# DAC_PWW_Outputs.net
KiCad netlist of a schematic drawn in Altium Designer
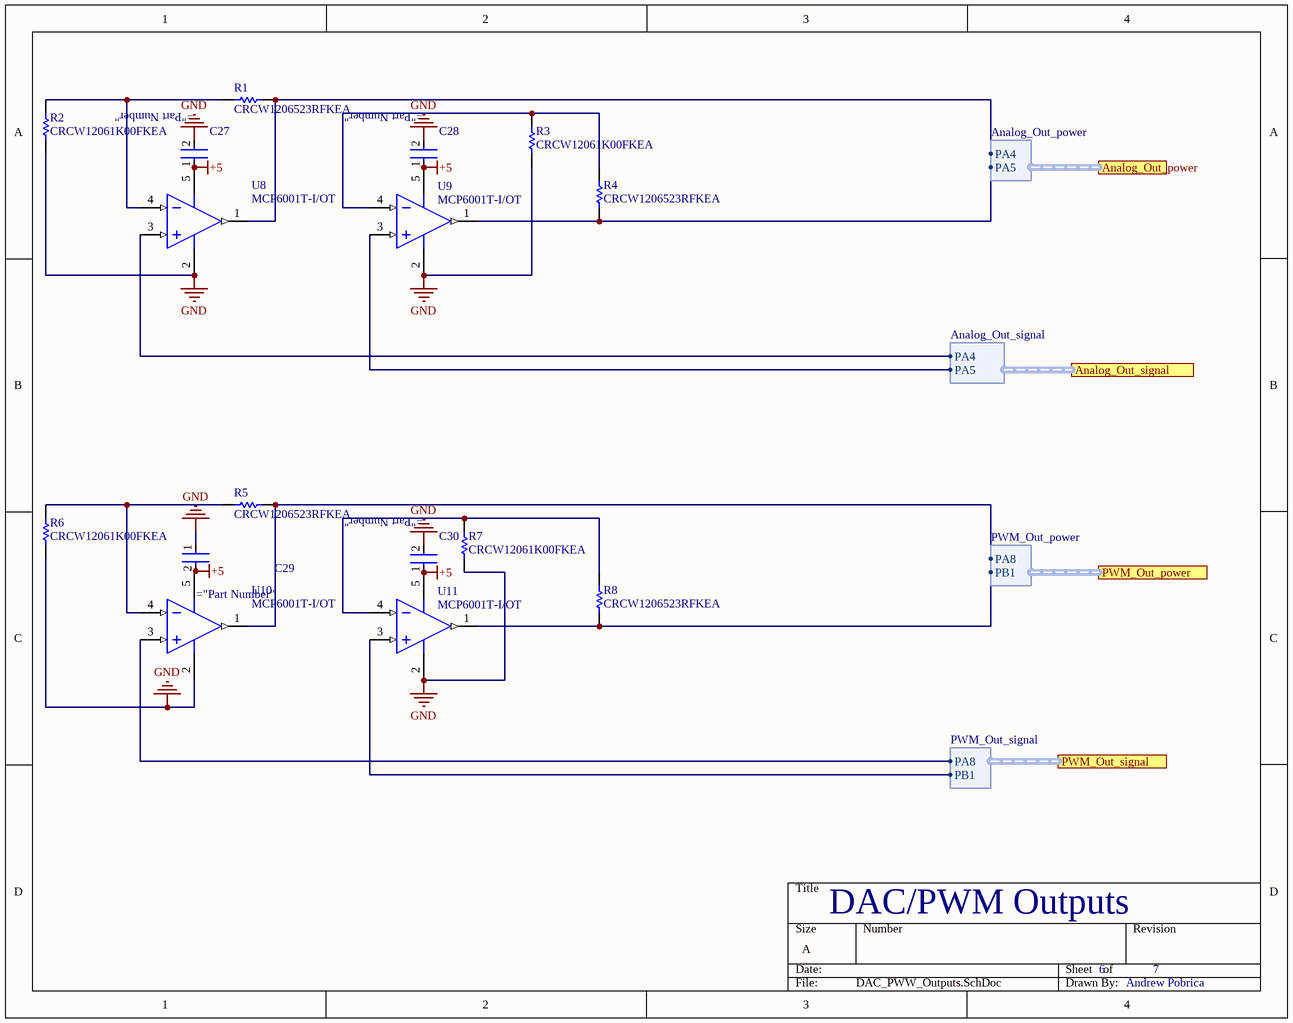
[diagram p0: DAC_PWW_Outputs.SchDoc]

(export (version "E")
  (design (tool "Eeschema 10.0.6"))
  (components
    (comp (ref "C27")
      (value "C0603C104K5RACTU")
      (footprint "Kemet_C0805_IPC_A")
      (libsource (lib "UNK_Kemet_C0603C104K5RACTU_eec") (part "C0603C104K5RACTU"))
    )
    (comp (ref "C28")
      (value "C0603C104K5RACTU")
      (footprint "Kemet_C0805_IPC_A")
      (libsource (lib "UNK_Kemet_C0603C104K5RACTU_eec") (part "C0603C104K5RACTU"))
    )
    (comp (ref "C29")
      (value "C0603C104K5RACTU")
      (footprint "Kemet_C0805_IPC_A")
      (libsource (lib "UNK_Kemet_C0603C104K5RACTU_eec") (part "C0603C104K5RACTU"))
    )
    (comp (ref "C30")
      (value "C0603C104K5RACTU")
      (footprint "Kemet_C0805_IPC_A")
      (libsource (lib "UNK_Kemet_C0603C104K5RACTU_eec") (part "C0603C104K5RACTU"))
    )
    (comp (ref "R1")
      (value "CRCW1206523RFKEA")
      (footprint "RESC3216X60X45NL10T20")
      (fields (field (name "MANUFACTURER") "Vishay Dale"))
      (libsource (lib "Altium Content Vault") (part "RES"))
    )
    (comp (ref "R2")
      (value "CRCW12061K00FKEA")
      (footprint "RESC3216X60X45ML15T20")
      (description "Chip Resistor, 1 KOhm, +/- 1%, 0.25 W, -55 to 155 degC, 1206 (3216 Metric), RoHS, Tape and Reel")
      (fields (field (name "MANUFACTURER") "Vishay Semiconductor") (field (name "TOLERANCE") "1%"))
      (libsource (lib "Altium Content Vault") (part "RES-2"))
    )
    (comp (ref "R3")
      (value "CRCW12061K00FKEA")
      (footprint "RESC3216X60X45ML15T20")
      (description "Chip Resistor, 1 KOhm, +/- 1%, 0.25 W, -55 to 155 degC, 1206 (3216 Metric), RoHS, Tape and Reel")
      (fields (field (name "MANUFACTURER") "Vishay Semiconductor") (field (name "TOLERANCE") "1%"))
      (libsource (lib "Altium Content Vault") (part "RES-2"))
    )
    (comp (ref "R4")
      (value "CRCW1206523RFKEA")
      (footprint "RESC3216X60X45NL10T20")
      (fields (field (name "MANUFACTURER") "Vishay Dale"))
      (libsource (lib "Altium Content Vault") (part "RES"))
    )
    (comp (ref "R5")
      (value "CRCW1206523RFKEA")
      (footprint "RESC3216X60X45NL10T20")
      (fields (field (name "MANUFACTURER") "Vishay Dale"))
      (libsource (lib "Altium Content Vault") (part "RES"))
    )
    (comp (ref "R6")
      (value "CRCW12061K00FKEA")
      (footprint "RESC3216X60X45ML15T20")
      (description "Chip Resistor, 1 KOhm, +/- 1%, 0.25 W, -55 to 155 degC, 1206 (3216 Metric), RoHS, Tape and Reel")
      (fields (field (name "MANUFACTURER") "Vishay Semiconductor") (field (name "TOLERANCE") "1%"))
      (libsource (lib "Altium Content Vault") (part "RES-2"))
    )
    (comp (ref "R7")
      (value "CRCW12061K00FKEA")
      (footprint "RESC3216X60X45ML15T20")
      (description "Chip Resistor, 1 KOhm, +/- 1%, 0.25 W, -55 to 155 degC, 1206 (3216 Metric), RoHS, Tape and Reel")
      (fields (field (name "MANUFACTURER") "Vishay Semiconductor") (field (name "TOLERANCE") "1%"))
      (libsource (lib "Altium Content Vault") (part "RES-2"))
    )
    (comp (ref "R8")
      (value "CRCW1206523RFKEA")
      (footprint "RESC3216X60X45NL10T20")
      (fields (field (name "MANUFACTURER") "Vishay Dale"))
      (libsource (lib "Altium Content Vault") (part "RES"))
    )
    (comp (ref "U8")
      (value "MCP6001T-I/OT")
      (footprint "SOT-23-OT5_CUSTOM")
      (description "1 MHz, Low-Power Operational Amplifier, 5-Pin SOT-23, Industrial Temperature, Tape and Reel")
      (libsource (lib "Components - 19.05.19 - 16.13") (part "AMP-OPA-MCP6001-SOT5"))
    )
    (comp (ref "U9")
      (value "MCP6001T-I/OT")
      (footprint "SOT-23-OT5_CUSTOM")
      (description "1 MHz, Low-Power Operational Amplifier, 5-Pin SOT-23, Industrial Temperature, Tape and Reel")
      (libsource (lib "Components - 19.05.19 - 16.13") (part "AMP-OPA-MCP6001-SOT5"))
    )
    (comp (ref "U10")
      (value "MCP6001T-I/OT")
      (footprint "SOT-23-OT5_CUSTOM")
      (description "1 MHz, Low-Power Operational Amplifier, 5-Pin SOT-23, Industrial Temperature, Tape and Reel")
      (libsource (lib "Components - 19.05.19 - 16.13") (part "AMP-OPA-MCP6001-SOT5"))
    )
    (comp (ref "U11")
      (value "MCP6001T-I/OT")
      (footprint "SOT-23-OT5_CUSTOM")
      (description "1 MHz, Low-Power Operational Amplifier, 5-Pin SOT-23, Industrial Temperature, Tape and Reel")
      (libsource (lib "Components - 19.05.19 - 16.13") (part "AMP-OPA-MCP6001-SOT5"))
    )
  )
  (nets
    (net (code "5") (name "+5") (class "Default")
      (node (ref "C27") (pin "1") (pinfunction "1_1") (pintype "passive"))
      (node (ref "C28") (pin "1") (pinfunction "1_1") (pintype "passive"))
      (node (ref "C29") (pin "2") (pinfunction "2_2") (pintype "passive"))
      (node (ref "C30") (pin "1") (pinfunction "1_1") (pintype "passive"))
      (node (ref "U10") (pin "5") (pinfunction "VDD_5") (pintype "power_in"))
      (node (ref "U11") (pin "5") (pinfunction "VDD_5") (pintype "power_in"))
      (node (ref "U8") (pin "5") (pinfunction "VDD_5") (pintype "power_in"))
      (node (ref "U9") (pin "5") (pinfunction "VDD_5") (pintype "power_in"))
    )
    (net (code "10") (name "GND") (class "Default")
      (node (ref "C27") (pin "2") (pinfunction "2_2") (pintype "passive"))
      (node (ref "C28") (pin "2") (pinfunction "2_2") (pintype "passive"))
      (node (ref "C29") (pin "1") (pinfunction "1_1") (pintype "passive"))
      (node (ref "C30") (pin "2") (pinfunction "2_2") (pintype "passive"))
      (node (ref "R2") (pin "2") (pinfunction "2_2") (pintype "passive"))
      (node (ref "R3") (pin "2") (pinfunction "2_2") (pintype "passive"))
      (node (ref "R6") (pin "2") (pinfunction "2_2") (pintype "passive"))
      (node (ref "R7") (pin "2") (pinfunction "2_2") (pintype "passive"))
      (node (ref "U10") (pin "2") (pinfunction "VSS_2") (pintype "power_in"))
      (node (ref "U11") (pin "2") (pinfunction "VSS_2") (pintype "power_in"))
      (node (ref "U8") (pin "2") (pinfunction "VSS_2") (pintype "power_in"))
      (node (ref "U9") (pin "2") (pinfunction "VSS_2") (pintype "power_in"))
    )
    (net (code "11") (name "Net-(U8-VIN-)") (class "Default")
      (node (ref "R1") (pin "2") (pinfunction "2_2") (pintype "passive"))
      (node (ref "R2") (pin "1") (pinfunction "1_1") (pintype "passive"))
      (node (ref "U8") (pin "4") (pinfunction "VIN-_4") (pintype "input"))
    )
    (net (code "12") (name "Net-(U8-VOUT)") (class "Default")
      (node (ref "R1") (pin "1") (pinfunction "1_1") (pintype "passive"))
      (node (ref "U8") (pin "1") (pinfunction "VOUT_1") (pintype "output"))
    )
    (net (code "13") (name "Net-(U9-VIN-)") (class "Default")
      (node (ref "R3") (pin "1") (pinfunction "1_1") (pintype "passive"))
      (node (ref "R4") (pin "2") (pinfunction "2_2") (pintype "passive"))
      (node (ref "U9") (pin "4") (pinfunction "VIN-_4") (pintype "input"))
    )
    (net (code "14") (name "Net-(U9-VOUT)") (class "Default")
      (node (ref "R4") (pin "1") (pinfunction "1_1") (pintype "passive"))
      (node (ref "U9") (pin "1") (pinfunction "VOUT_1") (pintype "output"))
    )
    (net (code "15") (name "Net-(U10-VIN-)") (class "Default")
      (node (ref "R5") (pin "2") (pinfunction "2_2") (pintype "passive"))
      (node (ref "R6") (pin "1") (pinfunction "1_1") (pintype "passive"))
      (node (ref "U10") (pin "4") (pinfunction "VIN-_4") (pintype "input"))
    )
    (net (code "16") (name "Net-(U10-VOUT)") (class "Default")
      (node (ref "R5") (pin "1") (pinfunction "1_1") (pintype "passive"))
      (node (ref "U10") (pin "1") (pinfunction "VOUT_1") (pintype "output"))
    )
    (net (code "17") (name "Net-(U11-VIN-)") (class "Default")
      (node (ref "R7") (pin "1") (pinfunction "1_1") (pintype "passive"))
      (node (ref "R8") (pin "2") (pinfunction "2_2") (pintype "passive"))
      (node (ref "U11") (pin "4") (pinfunction "VIN-_4") (pintype "input"))
    )
    (net (code "18") (name "Net-(U11-VOUT)") (class "Default")
      (node (ref "R8") (pin "1") (pinfunction "1_1") (pintype "passive"))
      (node (ref "U11") (pin "1") (pinfunction "VOUT_1") (pintype "output"))
    )
    (net (code "19") (name "unconnected-(U8-VIN+-Pad3)") (class "Default")
      (node (ref "U8") (pin "3") (pinfunction "VIN+_3") (pintype "input"))
    )
    (net (code "20") (name "unconnected-(U9-VIN+-Pad3)") (class "Default")
      (node (ref "U9") (pin "3") (pinfunction "VIN+_3") (pintype "input"))
    )
    (net (code "21") (name "unconnected-(U10-VIN+-Pad3)") (class "Default")
      (node (ref "U10") (pin "3") (pinfunction "VIN+_3") (pintype "input"))
    )
    (net (code "22") (name "unconnected-(U11-VIN+-Pad3)") (class "Default")
      (node (ref "U11") (pin "3") (pinfunction "VIN+_3") (pintype "input"))
    )
  )
)
